# zigbee-coordinator-router.net
KiCad netlist of a schematic drawn in Altium Designer
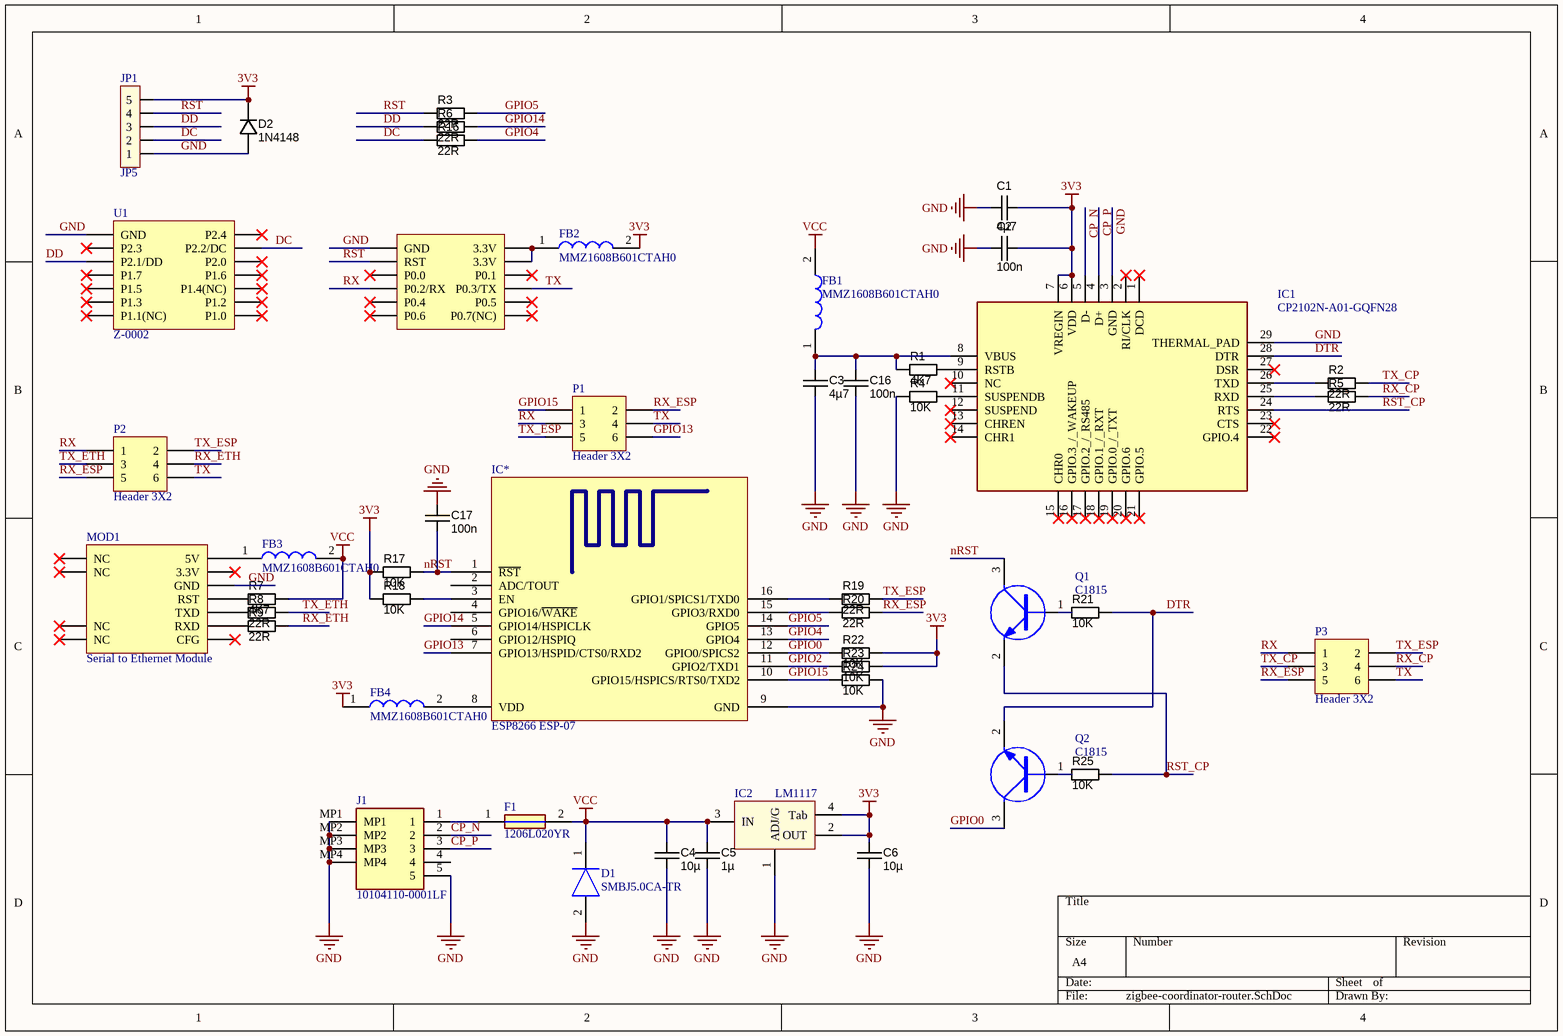
[diagram p0: zigbee-coordinator-router.SchDoc]

(export (version "E")
  (design (tool "Eeschema 10.0.6"))
  (components
    (comp (ref "C1")
      (value "4µ7")
      (footprint "CAPC2012N")
      (description "Capacitor SMD Cer 4.7uF 10% 16V X5R 0805")
      (fields (field (name "TOLERANCE") "±10%") (field (name "Comment") "approved sub OK"))
      (libsource (lib "PBL - Capacitors") (part "CAPC_4u7_0805"))
    )
    (comp (ref "C2")
      (value "100n")
      (footprint "CAPC1608N")
      (description "Capacitor SMD Cer 100nF 10% 50V X7R 0603")
      (fields (field (name "TOLERANCE") "±10%") (field (name "Comment") "approved sub OK"))
      (libsource (lib "PBL - Capacitors") (part "CAPC_100n_0603"))
    )
    (comp (ref "C3")
      (value "4µ7")
      (footprint "CAPC2012N")
      (description "Capacitor SMD Cer 4.7uF 10% 16V X5R 0805")
      (fields (field (name "TOLERANCE") "±10%") (field (name "Comment") "approved sub OK"))
      (libsource (lib "PBL - Capacitors") (part "CAPC_4u7_0805"))
    )
    (comp (ref "C4")
      (value "10µ")
      (footprint "CAPC2012N")
      (description "Capacitor SMD Cer 10uF 10% 16V X7R 0805")
      (fields (field (name "TOLERANCE") "±10%") (field (name "Comment") "approved sub OK"))
      (libsource (lib "PBL - Capacitors") (part "CAPC_10u_0805_16V"))
    )
    (comp (ref "C5")
      (value "1µ")
      (footprint "CAPC1608N")
      (description "Capacitor SMD Cer 1uF 10% 16V X7R 0603")
      (fields (field (name "TOLERANCE") "±10%") (field (name "Comment") "approved sub OK"))
      (libsource (lib "PBL - Capacitors") (part "CAPC_1u_0603"))
    )
    (comp (ref "C6")
      (value "10µ")
      (footprint "CAPC2012N")
      (description "Capacitor SMD Cer 10uF 10% 16V X7R 0805")
      (fields (field (name "TOLERANCE") "±10%") (field (name "Comment") "approved sub OK"))
      (libsource (lib "PBL - Capacitors") (part "CAPC_10u_0805_16V"))
    )
    (comp (ref "C16")
      (value "100n")
      (footprint "CAPC1608N")
      (description "Capacitor SMD Cer 100nF 10% 50V X7R 0603")
      (fields (field (name "TOLERANCE") "±10%") (field (name "Comment") "approved sub OK"))
      (libsource (lib "PBL - Capacitors") (part "CAPC_100n_0603"))
    )
    (comp (ref "C17")
      (value "100n")
      (footprint "CAPC1608N")
      (description "Capacitor SMD Cer 100nF 10% 50V X7R 0603")
      (fields (field (name "TOLERANCE") "±10%") (field (name "Comment") "approved sub OK"))
      (libsource (lib "PBL - Capacitors") (part "CAPC_100n_0603"))
    )
    (comp (ref "D1")
      (value "SMBJ5.0CA-TR")
      (footprint "SamacSys:SMBJ36CATR")
      (description "Diode")
      (fields (field (name "MOUSER PART NUMBER") "511-SMBJ5.0CA"))
      (libsource (lib "*") (part "SMBJ5.0CA-TR"))
    )
    (comp (ref "D2")
      (value "1N4148")
      (footprint "SOD523F")
      (description "Diode SMD small signal 0.2A SOD-523F")
      (libsource (lib "PBL - Diodes") (part "DIODE_1N4148_200mA_SOD523F"))
    )
    (comp (ref "F1")
      (value "1206L020YR")
      (footprint "SamacSys:FUSC3216X100N")
      (description "Fuse")
      (fields (field (name "MOUSER PART NUMBER") "576-1206L020YR"))
      (libsource (lib "SamacSys") (part "1206L020YR"))
    )
    (comp (ref "FB1")
      (value "MMZ1608B601CTAH0")
      (footprint "SamacSys:BEADC1608X95N")
      (description "Ferrite Bead")
      (fields (field (name "MOUSER PART NUMBER") "810-MMZ1608B601CTAH0"))
      (libsource (lib "") (part "MMZ1608B601CTAH0_1"))
    )
    (comp (ref "FB2")
      (value "MMZ1608B601CTAH0")
      (footprint "SamacSys:BEADC1608X95N")
      (description "Ferrite Bead")
      (fields (field (name "MOUSER PART NUMBER") "810-MMZ1608B601CTAH0"))
      (libsource (lib "SamacSys") (part "MMZ1608B601CTAH0"))
    )
    (comp (ref "FB3")
      (value "MMZ1608B601CTAH0")
      (footprint "SamacSys:BEADC1608X95N")
      (description "Ferrite Bead")
      (fields (field (name "MOUSER PART NUMBER") "810-MMZ1608B601CTAH0"))
      (libsource (lib "SamacSys") (part "MMZ1608B601CTAH0"))
    )
    (comp (ref "FB4")
      (value "MMZ1608B601CTAH0")
      (footprint "SamacSys:BEADC1608X95N")
      (description "Ferrite Bead")
      (fields (field (name "MOUSER PART NUMBER") "810-MMZ1608B601CTAH0"))
      (libsource (lib "SamacSys") (part "MMZ1608B601CTAH0"))
    )
    (comp (ref "IC*")
      (value "ESP8266 ESP-07")
      (footprint "ESP8266 ESP-07")
      (libsource (lib "ESP8266") (part "ESP8266 ESP-07"))
    )
    (comp (ref "IC1")
      (value "CP2102N-A01-GQFN28")
      (footprint "SamacSys:QFN50P500X500X80-29N-D")
      (description "Integrated Circuit")
      (fields (field (name "MOUSER PART NUMBER") "634-CP2102NA01GQFN28"))
      (libsource (lib "*") (part "CP2102N-A01-GQFN28"))
    )
    (comp (ref "IC2")
      (value "LM1117")
      (footprint "heromap:SOT223-4N")
      (description "3v3")
      (libsource (lib "heromap") (part "LM1117"))
    )
    (comp (ref "J1")
      (value "10104110-0001LF")
      (footprint "SamacSys:101041100001LF")
      (description "Connector")
      (fields (field (name "MOUSER PART NUMBER") "649-10104110-0001LF"))
      (libsource (lib "*") (part "10104110-0001LF"))
    )
    (comp (ref "JP1") (value "JP5") (footprint "JP5") (libsource (lib "Tr.Thoai") (part "JP5")))
    (comp (ref "MOD1")
      (value "Serial to Ethernet Module")
      (footprint "USR-TCP232-T2")
      (libsource (lib "SamacSys") (part "USR-TCP232-T2"))
    )
    (comp (ref "P1")
      (value "Header 3X2")
      (footprint "heromap:HDR2X3")
      (description "Header, 3-Pin, Dual row")
      (fields (field (name "PUBLISHER") "Altium Limited"))
      (libsource (lib "heromap") (part "Header 3X2"))
    )
    (comp (ref "P2")
      (value "Header 3X2")
      (footprint "heromap:HDR2X3")
      (description "Header, 3-Pin, Dual row")
      (fields (field (name "PUBLISHER") "Altium Limited"))
      (libsource (lib "heromap") (part "Header 3X2"))
    )
    (comp (ref "P3")
      (value "Header 3X2")
      (footprint "heromap:HDR2X3")
      (description "Header, 3-Pin, Dual row")
      (fields (field (name "PUBLISHER") "Altium Limited"))
      (libsource (lib "heromap") (part "Header 3X2"))
    )
    (comp (ref "Q1")
      (value "C1815")
      (footprint "heromap:SOT23")
      (description "NPN 600mW, ECB")
      (libsource (lib "heromap") (part "C1815"))
    )
    (comp (ref "Q2")
      (value "C1815")
      (footprint "heromap:SOT23")
      (description "NPN 600mW, ECB")
      (libsource (lib "heromap") (part "C1815"))
    )
    (comp (ref "R1")
      (value "4K7")
      (footprint "RESC1608N")
      (description "Resistor SMD chip 4.7k Ohm 0.1W 5% 0603")
      (fields (field (name "TOLERANCE") "±5%") (field (name "Comment") "Thick Film"))
      (libsource (lib "PBL - Resistors") (part "RES_4K7_0603_5%"))
    )
    (comp (ref "R2")
      (value "22R")
      (footprint "RESC1608N")
      (description "Resistor SMD chip 22 Ohm 0.1W 5% 0603")
      (fields (field (name "TOLERANCE") "±5%") (field (name "Comment") "Thick Film"))
      (libsource (lib "PBL - Resistors") (part "RES_22R_0603_5%"))
    )
    (comp (ref "R3")
      (value "22R")
      (footprint "RESC1608N")
      (description "Resistor SMD chip 22 Ohm 0.1W 5% 0603")
      (fields (field (name "TOLERANCE") "±5%") (field (name "Comment") "Thick Film"))
      (libsource (lib "PBL - Resistors") (part "RES_22R_0603_5%"))
    )
    (comp (ref "R4")
      (value "10K")
      (footprint "RESC1608N")
      (description "Resistor SMD chip 10k Ohm 0.1W 5% 0603")
      (fields (field (name "TOLERANCE") "±5%") (field (name "Comment") "Thick Film"))
      (libsource (lib "PBL - Resistors") (part "RES_10K_0603_5%"))
    )
    (comp (ref "R5")
      (value "22R")
      (footprint "RESC1608N")
      (description "Resistor SMD chip 22 Ohm 0.1W 5% 0603")
      (fields (field (name "TOLERANCE") "±5%") (field (name "Comment") "Thick Film"))
      (libsource (lib "PBL - Resistors") (part "RES_22R_0603_5%"))
    )
    (comp (ref "R6")
      (value "22R")
      (footprint "RESC1608N")
      (description "Resistor SMD chip 22 Ohm 0.1W 5% 0603")
      (fields (field (name "TOLERANCE") "±5%") (field (name "Comment") "Thick Film"))
      (libsource (lib "PBL - Resistors") (part "RES_22R_0603_5%"))
    )
    (comp (ref "R7")
      (value "4K7")
      (footprint "RESC1608N")
      (description "Resistor SMD chip 4.7k Ohm 0.1W 5% 0603")
      (fields (field (name "TOLERANCE") "±5%") (field (name "Comment") "Thick Film"))
      (libsource (lib "PBL - Resistors") (part "RES_4K7_0603_5%"))
    )
    (comp (ref "R8")
      (value "22R")
      (footprint "RESC1608N")
      (description "Resistor SMD chip 22 Ohm 0.1W 5% 0603")
      (fields (field (name "TOLERANCE") "±5%") (field (name "Comment") "Thick Film"))
      (libsource (lib "PBL - Resistors") (part "RES_22R_0603_5%"))
    )
    (comp (ref "R9")
      (value "22R")
      (footprint "RESC1608N")
      (description "Resistor SMD chip 22 Ohm 0.1W 5% 0603")
      (fields (field (name "TOLERANCE") "±5%") (field (name "Comment") "Thick Film"))
      (libsource (lib "PBL - Resistors") (part "RES_22R_0603_5%"))
    )
    (comp (ref "R16")
      (value "22R")
      (footprint "RESC1608N")
      (description "Resistor SMD chip 22 Ohm 0.1W 5% 0603")
      (fields (field (name "TOLERANCE") "±5%") (field (name "Comment") "Thick Film"))
      (libsource (lib "PBL - Resistors") (part "RES_22R_0603_5%"))
    )
    (comp (ref "R17")
      (value "10K")
      (footprint "RESC1608N")
      (description "Resistor SMD chip 10k Ohm 0.1W 5% 0603")
      (fields (field (name "TOLERANCE") "±5%") (field (name "Comment") "Thick Film"))
      (libsource (lib "PBL - Resistors") (part "RES_10K_0603_5%"))
    )
    (comp (ref "R18")
      (value "10K")
      (footprint "RESC1608N")
      (description "Resistor SMD chip 10k Ohm 0.1W 5% 0603")
      (fields (field (name "TOLERANCE") "±5%") (field (name "Comment") "Thick Film"))
      (libsource (lib "PBL - Resistors") (part "RES_10K_0603_5%"))
    )
    (comp (ref "R19")
      (value "22R")
      (footprint "RESC1608N")
      (description "Resistor SMD chip 22 Ohm 0.1W 5% 0603")
      (fields (field (name "TOLERANCE") "±5%") (field (name "Comment") "Thick Film"))
      (libsource (lib "PBL - Resistors") (part "RES_22R_0603_5%"))
    )
    (comp (ref "R20")
      (value "22R")
      (footprint "RESC1608N")
      (description "Resistor SMD chip 22 Ohm 0.1W 5% 0603")
      (fields (field (name "TOLERANCE") "±5%") (field (name "Comment") "Thick Film"))
      (libsource (lib "PBL - Resistors") (part "RES_22R_0603_5%"))
    )
    (comp (ref "R21")
      (value "10K")
      (footprint "RESC1608N")
      (description "Resistor SMD chip 10k Ohm 0.1W 5% 0603")
      (fields (field (name "TOLERANCE") "±5%") (field (name "Comment") "Thick Film"))
      (libsource (lib "PBL - Resistors") (part "RES_10K_0603_5%"))
    )
    (comp (ref "R22")
      (value "10K")
      (footprint "RESC1608N")
      (description "Resistor SMD chip 10k Ohm 0.1W 5% 0603")
      (fields (field (name "TOLERANCE") "±5%") (field (name "Comment") "Thick Film"))
      (libsource (lib "PBL - Resistors") (part "RES_10K_0603_5%"))
    )
    (comp (ref "R23")
      (value "10K")
      (footprint "RESC1608N")
      (description "Resistor SMD chip 10k Ohm 0.1W 5% 0603")
      (fields (field (name "TOLERANCE") "±5%") (field (name "Comment") "Thick Film"))
      (libsource (lib "PBL - Resistors") (part "RES_10K_0603_5%"))
    )
    (comp (ref "R24")
      (value "10K")
      (footprint "RESC1608N")
      (description "Resistor SMD chip 10k Ohm 0.1W 5% 0603")
      (fields (field (name "TOLERANCE") "±5%") (field (name "Comment") "Thick Film"))
      (libsource (lib "PBL - Resistors") (part "RES_10K_0603_5%"))
    )
    (comp (ref "R25")
      (value "10K")
      (footprint "RESC1608N")
      (description "Resistor SMD chip 10k Ohm 0.1W 5% 0603")
      (fields (field (name "TOLERANCE") "±5%") (field (name "Comment") "Thick Film"))
      (libsource (lib "PBL - Resistors") (part "RES_10K_0603_5%"))
    )
    (comp (ref "U1") (value "Z-0002") (footprint "Z-0002") (libsource (lib "SamacSys") (part "Z-0002")))
  )
  (nets
    (net (code "1") (name "/CP_N") (class "Default")
      (node (ref "IC1") (pin "5") (pinfunction "D-_5") (pintype "passive"))
      (node (ref "J1") (pin "2") (pinfunction "2_2") (pintype "passive"))
    )
    (net (code "2") (name "/CP_P") (class "Default")
      (node (ref "IC1") (pin "4") (pinfunction "D+_4") (pintype "passive"))
      (node (ref "J1") (pin "3") (pinfunction "3_3") (pintype "passive"))
    )
    (net (code "3") (name "/DC") (class "Default")
      (node (ref "JP1") (pin "2") (pinfunction "2_2") (pintype "passive"))
      (node (ref "R16") (pin "1") (pinfunction "1_1") (pintype "passive"))
      (node (ref "U1") (pin "4") (pinfunction "P2.2/DC_4") (pintype "passive"))
    )
    (net (code "4") (name "/DD") (class "Default")
      (node (ref "JP1") (pin "3") (pinfunction "3_3") (pintype "passive"))
      (node (ref "R6") (pin "1") (pinfunction "1_1") (pintype "passive"))
      (node (ref "U1") (pin "5") (pinfunction "P2.1/DD_5") (pintype "passive"))
    )
    (net (code "5") (name "/DTR") (class "Default")
      (node (ref "IC1") (pin "28") (pinfunction "DTR_28") (pintype "passive"))
      (node (ref "Q2") (pin "2") (pinfunction "E_2") (pintype "passive"))
      (node (ref "R21") (pin "2") (pinfunction "2_2") (pintype "passive"))
    )
    (net (code "6") (name "/GPIO0") (class "Default")
      (node (ref "IC*") (pin "12") (pinfunction "GPIO0/SPICS2_12") (pintype "passive"))
      (node (ref "Q2") (pin "3") (pinfunction "C_3") (pintype "passive"))
      (node (ref "R22") (pin "1") (pinfunction "1_1") (pintype "passive"))
    )
    (net (code "7") (name "/GPIO2") (class "Default")
      (node (ref "IC*") (pin "11") (pinfunction "GPIO2/TXD1_11") (pintype "passive"))
      (node (ref "R23") (pin "1") (pinfunction "1_1") (pintype "passive"))
    )
    (net (code "8") (name "/GPIO4") (class "Default")
      (node (ref "IC*") (pin "13") (pinfunction "GPIO4_13") (pintype "passive"))
      (node (ref "R16") (pin "2") (pinfunction "2_2") (pintype "passive"))
    )
    (net (code "9") (name "/GPIO5") (class "Default")
      (node (ref "IC*") (pin "14") (pinfunction "GPIO5_14") (pintype "passive"))
      (node (ref "R3") (pin "2") (pinfunction "2_2") (pintype "passive"))
    )
    (net (code "10") (name "/GPIO13") (class "Default")
      (node (ref "IC*") (pin "7") (pinfunction "GPIO13/HSPID/CTS0/RXD2_7") (pintype "passive"))
      (node (ref "P1") (pin "6") (pinfunction "6_6") (pintype "passive"))
    )
    (net (code "11") (name "/GPIO14") (class "Default")
      (node (ref "IC*") (pin "5") (pinfunction "GPIO14/HSPICLK_5") (pintype "passive"))
      (node (ref "R6") (pin "2") (pinfunction "2_2") (pintype "passive"))
    )
    (net (code "12") (name "/GPIO15") (class "Default")
      (node (ref "IC*") (pin "10") (pinfunction "GPIO15/HSPICS/RTS0/TXD2_10") (pintype "passive"))
      (node (ref "P1") (pin "1") (pinfunction "1_1") (pintype "passive"))
      (node (ref "R24") (pin "1") (pinfunction "1_1") (pintype "passive"))
    )
    (net (code "13") (name "/RST") (class "Default")
      (node (ref "JP1") (pin "4") (pinfunction "4_4") (pintype "passive"))
      (node (ref "R3") (pin "1") (pinfunction "1_1") (pintype "passive"))
      (node (ref "U1") (pin "17") (pinfunction "RST_17") (pintype "passive"))
    )
    (net (code "14") (name "/RST_CP") (class "Default")
      (node (ref "IC1") (pin "24") (pinfunction "RTS_24") (pintype "passive"))
      (node (ref "Q1") (pin "2") (pinfunction "E_2") (pintype "passive"))
      (node (ref "R25") (pin "2") (pinfunction "2_2") (pintype "passive"))
    )
    (net (code "15") (name "/RX") (class "Default")
      (node (ref "P1") (pin "3") (pinfunction "3_3") (pintype "passive"))
      (node (ref "P2") (pin "1") (pinfunction "1_1") (pintype "passive"))
      (node (ref "P3") (pin "1") (pinfunction "1_1") (pintype "passive"))
      (node (ref "U1") (pin "21") (pinfunction "P0.2/RX_21") (pintype "passive"))
    )
    (net (code "16") (name "/RX_CP") (class "Default")
      (node (ref "P3") (pin "4") (pinfunction "4_4") (pintype "passive"))
      (node (ref "R5") (pin "2") (pinfunction "2_2") (pintype "passive"))
    )
    (net (code "17") (name "/RX_ESP") (class "Default")
      (node (ref "P1") (pin "2") (pinfunction "2_2") (pintype "passive"))
      (node (ref "P2") (pin "5") (pinfunction "5_5") (pintype "passive"))
      (node (ref "P3") (pin "5") (pinfunction "5_5") (pintype "passive"))
      (node (ref "R20") (pin "2") (pinfunction "2_2") (pintype "passive"))
    )
    (net (code "18") (name "/RX_ETH") (class "Default")
      (node (ref "P2") (pin "4") (pinfunction "4_4") (pintype "passive"))
      (node (ref "R9") (pin "2") (pinfunction "2_2") (pintype "passive"))
    )
    (net (code "19") (name "/TX") (class "Default")
      (node (ref "P1") (pin "4") (pinfunction "4_4") (pintype "passive"))
      (node (ref "P2") (pin "6") (pinfunction "6_6") (pintype "passive"))
      (node (ref "P3") (pin "6") (pinfunction "6_6") (pintype "passive"))
      (node (ref "U1") (pin "22") (pinfunction "P0.3/TX_22") (pintype "passive"))
    )
    (net (code "20") (name "/TX_CP") (class "Default")
      (node (ref "P3") (pin "3") (pinfunction "3_3") (pintype "passive"))
      (node (ref "R2") (pin "2") (pinfunction "2_2") (pintype "passive"))
    )
    (net (code "21") (name "/TX_ESP") (class "Default")
      (node (ref "P1") (pin "5") (pinfunction "5_5") (pintype "passive"))
      (node (ref "P2") (pin "2") (pinfunction "2_2") (pintype "passive"))
      (node (ref "P3") (pin "2") (pinfunction "2_2") (pintype "passive"))
      (node (ref "R19") (pin "2") (pinfunction "2_2") (pintype "passive"))
    )
    (net (code "22") (name "/TX_ETH") (class "Default")
      (node (ref "P2") (pin "3") (pinfunction "3_3") (pintype "passive"))
      (node (ref "R8") (pin "2") (pinfunction "2_2") (pintype "passive"))
    )
    (net (code "23") (name "/nRST") (class "Default")
      (node (ref "C17") (pin "1") (pintype "passive"))
      (node (ref "IC*") (pin "1") (pinfunction "~{RST}_1") (pintype "passive"))
      (node (ref "Q1") (pin "3") (pinfunction "C_3") (pintype "passive"))
      (node (ref "R17") (pin "2") (pinfunction "2_2") (pintype "passive"))
    )
    (net (code "24") (name "3V3") (class "Default")
      (node (ref "C1") (pin "1") (pintype "passive"))
      (node (ref "C2") (pin "1") (pintype "passive"))
      (node (ref "C6") (pin "1") (pintype "passive"))
      (node (ref "D2") (pin "K") (pinfunction "K_K") (pintype "passive"))
      (node (ref "FB2") (pin "2") (pinfunction "2_2") (pintype "passive"))
      (node (ref "FB4") (pin "1") (pinfunction "1_1") (pintype "passive"))
      (node (ref "IC1") (pin "6") (pinfunction "VDD_6") (pintype "passive"))
      (node (ref "IC1") (pin "7") (pinfunction "VREGIN_7") (pintype "passive"))
      (node (ref "IC2") (pin "2") (pinfunction "OUT_2") (pintype "passive"))
      (node (ref "IC2") (pin "4") (pinfunction "Tab_4") (pintype "passive"))
      (node (ref "JP1") (pin "5") (pinfunction "5_5") (pintype "passive"))
      (node (ref "R17") (pin "1") (pinfunction "1_1") (pintype "passive"))
      (node (ref "R18") (pin "1") (pinfunction "1_1") (pintype "passive"))
      (node (ref "R22") (pin "2") (pinfunction "2_2") (pintype "passive"))
      (node (ref "R23") (pin "2") (pinfunction "2_2") (pintype "passive"))
    )
    (net (code "25") (name "GND") (class "Default")
      (node (ref "C1") (pin "2") (pintype "passive"))
      (node (ref "C16") (pin "2") (pintype "passive"))
      (node (ref "C17") (pin "2") (pintype "passive"))
      (node (ref "C2") (pin "2") (pintype "passive"))
      (node (ref "C3") (pin "2") (pintype "passive"))
      (node (ref "C4") (pin "2") (pintype "passive"))
      (node (ref "C5") (pin "2") (pintype "passive"))
      (node (ref "C6") (pin "2") (pintype "passive"))
      (node (ref "D1") (pin "2") (pinfunction "A_2") (pintype "passive"))
      (node (ref "D2") (pin "A") (pinfunction "A_A") (pintype "passive"))
      (node (ref "IC*") (pin "9") (pinfunction "GND_9") (pintype "passive"))
      (node (ref "IC1") (pin "29") (pinfunction "THERMAL_PAD_29") (pintype "passive"))
      (node (ref "IC1") (pin "3") (pinfunction "GND_3") (pintype "passive"))
      (node (ref "IC2") (pin "1") (pinfunction "ADJ/G_1") (pintype "passive"))
      (node (ref "J1") (pin "5") (pinfunction "5_5") (pintype "passive"))
      (node (ref "J1") (pin "MP1") (pinfunction "MP1_MP1") (pintype "passive"))
      (node (ref "J1") (pin "MP2") (pinfunction "MP2_MP2") (pintype "passive"))
      (node (ref "J1") (pin "MP3") (pinfunction "MP3_MP3") (pintype "passive"))
      (node (ref "J1") (pin "MP4") (pinfunction "MP4_MP4") (pintype "passive"))
      (node (ref "JP1") (pin "1") (pinfunction "1_1") (pintype "passive"))
      (node (ref "MOD1") (pin "3") (pinfunction "GND_3") (pintype "passive"))
      (node (ref "R24") (pin "2") (pinfunction "2_2") (pintype "passive"))
      (node (ref "R4") (pin "1") (pinfunction "1_1") (pintype "passive"))
      (node (ref "U1") (pin "1") (pinfunction "GND_1") (pintype "passive"))
      (node (ref "U1") (pin "15") (pinfunction "GND_15") (pintype "passive"))
    )
    (net (code "26") (name "Net-(F1-Pad1)") (class "Default")
      (node (ref "F1") (pin "1") (pinfunction "1_1") (pintype "passive"))
      (node (ref "J1") (pin "1") (pinfunction "1_1") (pintype "passive"))
    )
    (net (code "27") (name "Net-(FB2-Pad1)") (class "Default")
      (node (ref "FB2") (pin "1") (pinfunction "1_1") (pintype "passive"))
      (node (ref "U1") (pin "16") (pinfunction "3.3V_16") (pintype "passive"))
      (node (ref "U1") (pin "18") (pinfunction "3.3V_18") (pintype "passive"))
    )
    (net (code "28") (name "Net-(IC*-EN)") (class "Default")
      (node (ref "IC*") (pin "3") (pinfunction "EN_3") (pintype "passive"))
      (node (ref "R18") (pin "2") (pinfunction "2_2") (pintype "passive"))
    )
    (net (code "29") (name "Net-(IC*-GPIO1{slash}SPICS1{slash}TXD0)") (class "Default")
      (node (ref "IC*") (pin "16") (pinfunction "GPIO1/SPICS1/TXD0_16") (pintype "passive"))
      (node (ref "R19") (pin "1") (pinfunction "1_1") (pintype "passive"))
    )
    (net (code "30") (name "Net-(IC*-GPIO3{slash}RXD0)") (class "Default")
      (node (ref "IC*") (pin "15") (pinfunction "GPIO3/RXD0_15") (pintype "passive"))
      (node (ref "R20") (pin "1") (pinfunction "1_1") (pintype "passive"))
    )
    (net (code "31") (name "Net-(IC*-VDD)") (class "Default")
      (node (ref "FB4") (pin "2") (pinfunction "2_2") (pintype "passive"))
      (node (ref "IC*") (pin "8") (pinfunction "VDD_8") (pintype "passive"))
    )
    (net (code "32") (name "Net-(IC1-RSTB)") (class "Default")
      (node (ref "IC1") (pin "9") (pinfunction "RSTB_9") (pintype "passive"))
      (node (ref "R1") (pin "2") (pinfunction "2_2") (pintype "passive"))
    )
    (net (code "33") (name "Net-(IC1-RXD)") (class "Default")
      (node (ref "IC1") (pin "25") (pinfunction "RXD_25") (pintype "passive"))
      (node (ref "R5") (pin "1") (pinfunction "1_1") (pintype "passive"))
    )
    (net (code "34") (name "Net-(IC1-SUSPENDB)") (class "Default")
      (node (ref "IC1") (pin "11") (pinfunction "SUSPENDB_11") (pintype "passive"))
      (node (ref "R4") (pin "2") (pinfunction "2_2") (pintype "passive"))
    )
    (net (code "35") (name "Net-(IC1-TXD)") (class "Default")
      (node (ref "IC1") (pin "26") (pinfunction "TXD_26") (pintype "passive"))
      (node (ref "R2") (pin "1") (pinfunction "1_1") (pintype "passive"))
    )
    (net (code "36") (name "Net-(IC1-VBUS)") (class "Default")
      (node (ref "C16") (pin "1") (pintype "passive"))
      (node (ref "C3") (pin "1") (pintype "passive"))
      (node (ref "FB1") (pin "1") (pinfunction "1_1") (pintype "passive"))
      (node (ref "IC1") (pin "8") (pinfunction "VBUS_8") (pintype "passive"))
      (node (ref "R1") (pin "1") (pinfunction "1_1") (pintype "passive"))
    )
    (net (code "37") (name "Net-(MOD1-5V)") (class "Default")
      (node (ref "FB3") (pin "1") (pinfunction "1_1") (pintype "passive"))
      (node (ref "MOD1") (pin "1") (pinfunction "5V_1") (pintype "passive"))
    )
    (net (code "38") (name "Net-(MOD1-RST)") (class "Default")
      (node (ref "MOD1") (pin "4") (pinfunction "RST_4") (pintype "passive"))
      (node (ref "R7") (pin "1") (pinfunction "1_1") (pintype "passive"))
    )
    (net (code "39") (name "Net-(MOD1-RXD)") (class "Default")
      (node (ref "MOD1") (pin "6") (pinfunction "RXD_6") (pintype "passive"))
      (node (ref "R9") (pin "1") (pinfunction "1_1") (pintype "passive"))
    )
    (net (code "40") (name "Net-(MOD1-TXD)") (class "Default")
      (node (ref "MOD1") (pin "5") (pinfunction "TXD_5") (pintype "passive"))
      (node (ref "R8") (pin "1") (pinfunction "1_1") (pintype "passive"))
    )
    (net (code "41") (name "Net-(Q1-B)") (class "Default")
      (node (ref "Q1") (pin "1") (pinfunction "B_1") (pintype "passive"))
      (node (ref "R21") (pin "1") (pinfunction "1_1") (pintype "passive"))
    )
    (net (code "42") (name "Net-(Q2-B)") (class "Default")
      (node (ref "Q2") (pin "1") (pinfunction "B_1") (pintype "passive"))
      (node (ref "R25") (pin "1") (pinfunction "1_1") (pintype "passive"))
    )
    (net (code "43") (name "VCC") (class "Default")
      (node (ref "C4") (pin "1") (pintype "passive"))
      (node (ref "C5") (pin "1") (pintype "passive"))
      (node (ref "D1") (pin "1") (pinfunction "K_1") (pintype "passive"))
      (node (ref "F1") (pin "2") (pinfunction "2_2") (pintype "passive"))
      (node (ref "FB1") (pin "2") (pinfunction "2_2") (pintype "passive"))
      (node (ref "FB3") (pin "2") (pinfunction "2_2") (pintype "passive"))
      (node (ref "IC2") (pin "3") (pinfunction "IN_3") (pintype "passive"))
      (node (ref "R7") (pin "2") (pinfunction "2_2") (pintype "passive"))
    )
    (net (code "44") (name "unconnected-(IC*-ADC{slash}TOUT-Pad2)") (class "Default")
      (node (ref "IC*") (pin "2") (pinfunction "ADC/TOUT_2") (pintype "passive"))
    )
    (net (code "45") (name "unconnected-(IC*-GPIO12{slash}HSPIQ-Pad6)") (class "Default")
      (node (ref "IC*") (pin "6") (pinfunction "GPIO12/HSPIQ_6") (pintype "passive"))
    )
    (net (code "46") (name "unconnected-(IC*-GPIO16{slash}~{WAKE}-Pad4)") (class "Default")
      (node (ref "IC*") (pin "4") (pinfunction "GPIO16/~{WAKE}_4") (pintype "passive"))
    )
    (net (code "47") (name "unconnected-(IC1-CHR0-Pad15)") (class "Default")
      (node (ref "IC1") (pin "15") (pinfunction "CHR0_15") (pintype "passive+no_connect"))
    )
    (net (code "48") (name "unconnected-(IC1-CHR1-Pad14)") (class "Default")
      (node (ref "IC1") (pin "14") (pinfunction "CHR1_14") (pintype "passive+no_connect"))
    )
    (net (code "49") (name "unconnected-(IC1-CHREN-Pad13)") (class "Default")
      (node (ref "IC1") (pin "13") (pinfunction "CHREN_13") (pintype "passive+no_connect"))
    )
    (net (code "50") (name "unconnected-(IC1-CTS-Pad23)") (class "Default")
      (node (ref "IC1") (pin "23") (pinfunction "CTS_23") (pintype "passive+no_connect"))
    )
    (net (code "51") (name "unconnected-(IC1-DCD-Pad1)") (class "Default")
      (node (ref "IC1") (pin "1") (pinfunction "DCD_1") (pintype "passive+no_connect"))
    )
    (net (code "52") (name "unconnected-(IC1-DSR-Pad27)") (class "Default")
      (node (ref "IC1") (pin "27") (pinfunction "DSR_27") (pintype "passive+no_connect"))
    )
    (net (code "53") (name "unconnected-(IC1-GPIO.0_{slash}_TXT-Pad19)") (class "Default")
      (node (ref "IC1") (pin "19") (pinfunction "GPIO.0_/_TXT_19") (pintype "passive+no_connect"))
    )
    (net (code "54") (name "unconnected-(IC1-GPIO.1_{slash}_RXT-Pad18)") (class "Default")
      (node (ref "IC1") (pin "18") (pinfunction "GPIO.1_/_RXT_18") (pintype "passive+no_connect"))
    )
    (net (code "55") (name "unconnected-(IC1-GPIO.2_{slash}_RS485-Pad17)") (class "Default")
      (node (ref "IC1") (pin "17") (pinfunction "GPIO.2_/_RS485_17") (pintype "passive+no_connect"))
    )
    (net (code "56") (name "unconnected-(IC1-GPIO.3_{slash}_WAKEUP-Pad16)") (class "Default")
      (node (ref "IC1") (pin "16") (pinfunction "GPIO.3_/_WAKEUP_16") (pintype "passive+no_connect"))
    )
    (net (code "57") (name "unconnected-(IC1-GPIO.4-Pad22)") (class "Default")
      (node (ref "IC1") (pin "22") (pinfunction "GPIO.4_22") (pintype "passive+no_connect"))
    )
    (net (code "58") (name "unconnected-(IC1-GPIO.5-Pad21)") (class "Default")
      (node (ref "IC1") (pin "21") (pinfunction "GPIO.5_21") (pintype "passive+no_connect"))
    )
    (net (code "59") (name "unconnected-(IC1-GPIO.6-Pad20)") (class "Default")
      (node (ref "IC1") (pin "20") (pinfunction "GPIO.6_20") (pintype "passive+no_connect"))
    )
    (net (code "60") (name "unconnected-(IC1-NC-Pad10)") (class "Default")
      (node (ref "IC1") (pin "10") (pinfunction "NC_10") (pintype "passive+no_connect"))
    )
    (net (code "61") (name "unconnected-(IC1-RI{slash}CLK-Pad2)") (class "Default")
      (node (ref "IC1") (pin "2") (pinfunction "RI/CLK_2") (pintype "passive+no_connect"))
    )
    (net (code "62") (name "unconnected-(IC1-SUSPEND-Pad12)") (class "Default")
      (node (ref "IC1") (pin "12") (pinfunction "SUSPEND_12") (pintype "passive+no_connect"))
    )
    (net (code "63") (name "unconnected-(J1-Pad4)") (class "Default")
      (node (ref "J1") (pin "4") (pinfunction "4_4") (pintype "passive"))
    )
    (net (code "64") (name "unconnected-(MOD1-3.3V-Pad2)") (class "Default")
      (node (ref "MOD1") (pin "2") (pinfunction "3.3V_2") (pintype "passive+no_connect"))
    )
    (net (code "65") (name "unconnected-(MOD1-CFG-Pad7)") (class "Default")
      (node (ref "MOD1") (pin "7") (pinfunction "CFG_7") (pintype "passive+no_connect"))
    )
    (net (code "66") (name "unconnected-(MOD1-NC-Pad0)") (class "Default")
      (node (ref "MOD1") (pin "0") (pinfunction "NC_0") (pintype "passive+no_connect"))
    )
    (net (code "67") (name "unconnected-(MOD1-NC-Pad0)_1") (class "Default")
      (node (ref "MOD1") (pin "0") (pinfunction "NC_0") (pintype "passive+no_connect"))
    )
    (net (code "68") (name "unconnected-(MOD1-NC-Pad0)_2") (class "Default")
      (node (ref "MOD1") (pin "0") (pinfunction "NC_0") (pintype "passive+no_connect"))
    )
    (net (code "69") (name "unconnected-(MOD1-NC-Pad0)_3") (class "Default")
      (node (ref "MOD1") (pin "0") (pinfunction "NC_0") (pintype "passive+no_connect"))
    )
    (net (code "70") (name "unconnected-(U1-P0.0-Pad19)") (class "Default")
      (node (ref "U1") (pin "19") (pinfunction "P0.0_19") (pintype "passive+no_connect"))
    )
    (net (code "71") (name "unconnected-(U1-P0.1-Pad20)") (class "Default")
      (node (ref "U1") (pin "20") (pinfunction "P0.1_20") (pintype "passive+no_connect"))
    )
    (net (code "72") (name "unconnected-(U1-P0.4-Pad23)") (class "Default")
      (node (ref "U1") (pin "23") (pinfunction "P0.4_23") (pintype "passive+no_connect"))
    )
    (net (code "73") (name "unconnected-(U1-P0.5-Pad24)") (class "Default")
      (node (ref "U1") (pin "24") (pinfunction "P0.5_24") (pintype "passive+no_connect"))
    )
    (net (code "74") (name "unconnected-(U1-P0.6-Pad25)") (class "Default")
      (node (ref "U1") (pin "25") (pinfunction "P0.6_25") (pintype "passive+no_connect"))
    )
    (net (code "75") (name "unconnected-(U1-P0.7(NC)-Pad26)") (class "Default")
      (node (ref "U1") (pin "26") (pinfunction "P0.7(NC)_26") (pintype "passive+no_connect"))
    )
    (net (code "76") (name "unconnected-(U1-P1.0-Pad14)") (class "Default")
      (node (ref "U1") (pin "14") (pinfunction "P1.0_14") (pintype "passive+no_connect"))
    )
    (net (code "77") (name "unconnected-(U1-P1.1(NC)-Pad13)") (class "Default")
      (node (ref "U1") (pin "13") (pinfunction "P1.1(NC)_13") (pintype "passive+no_connect"))
    )
    (net (code "78") (name "unconnected-(U1-P1.2-Pad12)") (class "Default")
      (node (ref "U1") (pin "12") (pinfunction "P1.2_12") (pintype "passive+no_connect"))
    )
    (net (code "79") (name "unconnected-(U1-P1.3-Pad11)") (class "Default")
      (node (ref "U1") (pin "11") (pinfunction "P1.3_11") (pintype "passive+no_connect"))
    )
    (net (code "80") (name "unconnected-(U1-P1.4(NC)-Pad10)") (class "Default")
      (node (ref "U1") (pin "10") (pinfunction "P1.4(NC)_10") (pintype "passive+no_connect"))
    )
    (net (code "81") (name "unconnected-(U1-P1.5-Pad9)") (class "Default")
      (node (ref "U1") (pin "9") (pinfunction "P1.5_9") (pintype "passive+no_connect"))
    )
    (net (code "82") (name "unconnected-(U1-P1.6-Pad8)") (class "Default")
      (node (ref "U1") (pin "8") (pinfunction "P1.6_8") (pintype "passive+no_connect"))
    )
    (net (code "83") (name "unconnected-(U1-P1.7-Pad7)") (class "Default")
      (node (ref "U1") (pin "7") (pinfunction "P1.7_7") (pintype "passive+no_connect"))
    )
    (net (code "84") (name "unconnected-(U1-P2.0-Pad6)") (class "Default")
      (node (ref "U1") (pin "6") (pinfunction "P2.0_6") (pintype "passive+no_connect"))
    )
    (net (code "85") (name "unconnected-(U1-P2.3-Pad3)") (class "Default")
      (node (ref "U1") (pin "3") (pinfunction "P2.3_3") (pintype "passive+no_connect"))
    )
    (net (code "86") (name "unconnected-(U1-P2.4-Pad2)") (class "Default")
      (node (ref "U1") (pin "2") (pinfunction "P2.4_2") (pintype "passive+no_connect"))
    )
  )
)
